# Adafruit_TFP401_to_40pin_TFT.net
KiCad netlist of a schematic drawn in EAGLE
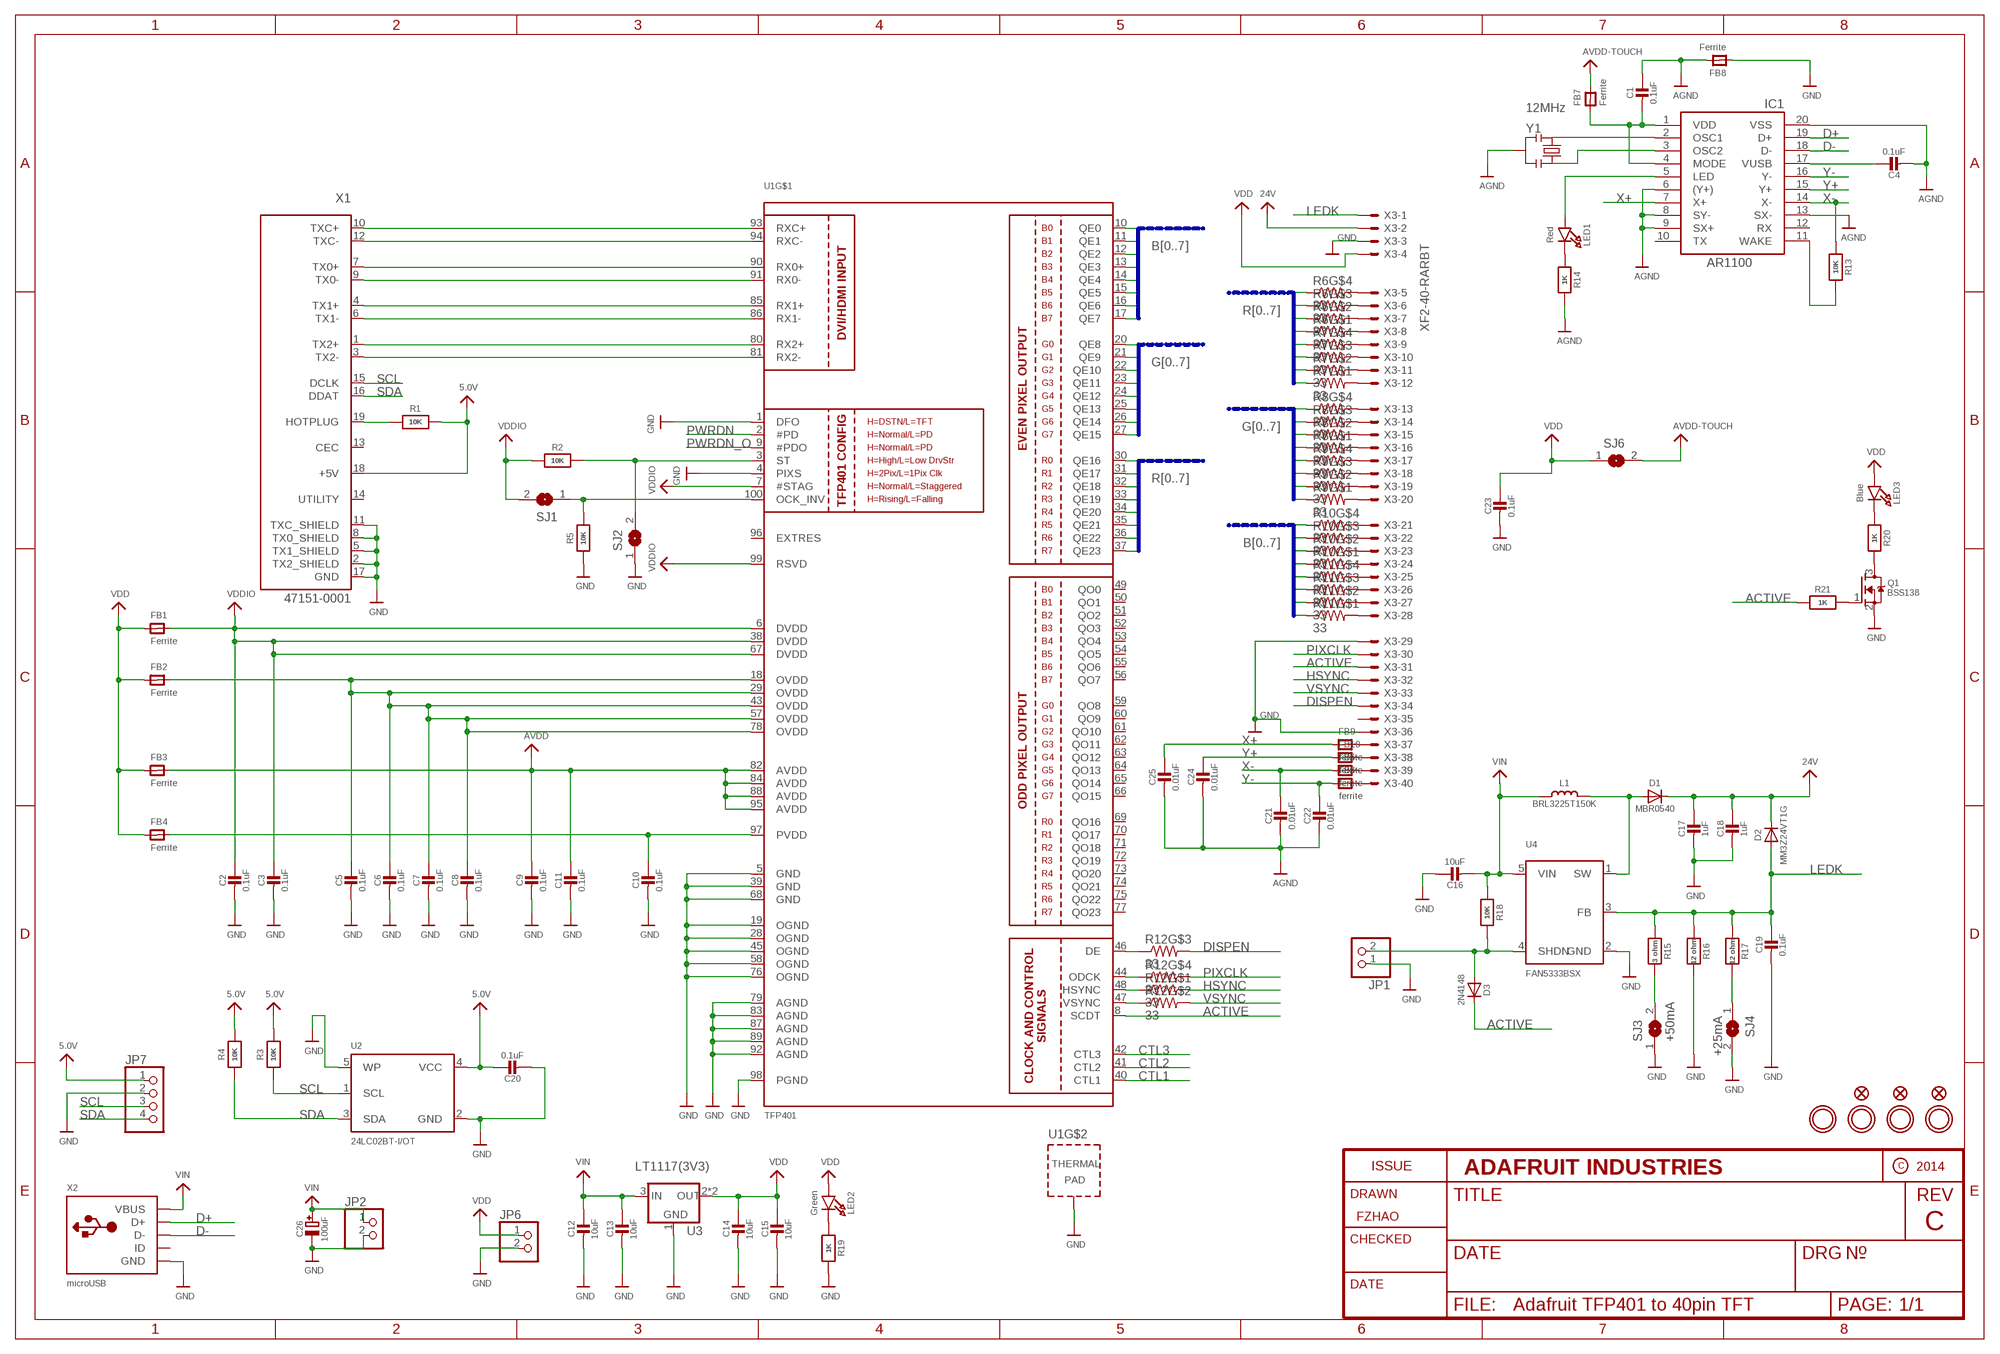
[diagram p0: schematic, sheet 1]

(export (version "E")
  (design (tool "Eeschema 10.0.6"))
  (components
    (comp (ref "C1")
      (value "0.1uF")
      (footprint "eagle-import:0805-NO")
      (libsource (lib "eagle-import") (part "CAP_CERAMIC0805-NOOUTLINE"))
    )
    (comp (ref "C2")
      (value "0.1uF")
      (footprint "eagle-import:0805-NO")
      (libsource (lib "eagle-import") (part "CAP_CERAMIC0805-NOOUTLINE"))
    )
    (comp (ref "C3")
      (value "0.1uF")
      (footprint "eagle-import:0805-NO")
      (libsource (lib "eagle-import") (part "CAP_CERAMIC0805-NOOUTLINE"))
    )
    (comp (ref "C4")
      (value "0.1uF")
      (footprint "eagle-import:0805-NO")
      (libsource (lib "eagle-import") (part "CAP_CERAMIC0805-NOOUTLINE"))
    )
    (comp (ref "C5")
      (value "0.1uF")
      (footprint "eagle-import:0805-NO")
      (libsource (lib "eagle-import") (part "CAP_CERAMIC0805-NOOUTLINE"))
    )
    (comp (ref "C6")
      (value "0.1uF")
      (footprint "eagle-import:_0805MP")
      (libsource (lib "eagle-import") (part "CAP_CERAMIC_0805MP"))
    )
    (comp (ref "C7")
      (value "0.1uF")
      (footprint "eagle-import:0805-NO")
      (libsource (lib "eagle-import") (part "CAP_CERAMIC0805-NOOUTLINE"))
    )
    (comp (ref "C8")
      (value "0.1uF")
      (footprint "eagle-import:0805-NO")
      (libsource (lib "eagle-import") (part "CAP_CERAMIC0805-NOOUTLINE"))
    )
    (comp (ref "C9")
      (value "0.1uF")
      (footprint "eagle-import:0805-NO")
      (libsource (lib "eagle-import") (part "CAP_CERAMIC0805-NOOUTLINE"))
    )
    (comp (ref "C10")
      (value "0.1uF")
      (footprint "eagle-import:0805-NO")
      (libsource (lib "eagle-import") (part "CAP_CERAMIC0805-NOOUTLINE"))
    )
    (comp (ref "C11")
      (value "0.1uF")
      (footprint "eagle-import:0805-NO")
      (libsource (lib "eagle-import") (part "CAP_CERAMIC0805-NOOUTLINE"))
    )
    (comp (ref "C12")
      (value "10uF")
      (footprint "eagle-import:0805-NO")
      (libsource (lib "eagle-import") (part "CAP_CERAMIC0805-NOOUTLINE"))
    )
    (comp (ref "C13")
      (value "10uF")
      (footprint "eagle-import:0805-NO")
      (libsource (lib "eagle-import") (part "CAP_CERAMIC0805-NOOUTLINE"))
    )
    (comp (ref "C14")
      (value "10uF")
      (footprint "eagle-import:0805-NO")
      (libsource (lib "eagle-import") (part "CAP_CERAMIC0805-NOOUTLINE"))
    )
    (comp (ref "C15")
      (value "10uF")
      (footprint "eagle-import:0805-NO")
      (libsource (lib "eagle-import") (part "CAP_CERAMIC0805-NOOUTLINE"))
    )
    (comp (ref "C16")
      (value "10uF")
      (footprint "eagle-import:0805-NO")
      (libsource (lib "eagle-import") (part "CAP_CERAMIC0805-NOOUTLINE"))
    )
    (comp (ref "C17")
      (value "1uF")
      (footprint "eagle-import:0805-NO")
      (libsource (lib "eagle-import") (part "CAP_CERAMIC0805-NOOUTLINE"))
    )
    (comp (ref "C18")
      (value "1uF")
      (footprint "eagle-import:0805-NO")
      (libsource (lib "eagle-import") (part "CAP_CERAMIC0805-NOOUTLINE"))
    )
    (comp (ref "C19")
      (value "0.1uF")
      (footprint "eagle-import:0805-NO")
      (libsource (lib "eagle-import") (part "CAP_CERAMIC0805-NOOUTLINE"))
    )
    (comp (ref "C20")
      (value "0.1uF")
      (footprint "eagle-import:0805-NO")
      (libsource (lib "eagle-import") (part "CAP_CERAMIC0805-NOOUTLINE"))
    )
    (comp (ref "C21")
      (value "0.01uF")
      (footprint "eagle-import:0805-NO")
      (libsource (lib "eagle-import") (part "CAP_CERAMIC0805-NOOUTLINE"))
    )
    (comp (ref "C22")
      (value "0.01uF")
      (footprint "eagle-import:0805-NO")
      (libsource (lib "eagle-import") (part "CAP_CERAMIC0805-NOOUTLINE"))
    )
    (comp (ref "C23")
      (value "0.1uF")
      (footprint "eagle-import:0805-NO")
      (libsource (lib "eagle-import") (part "CAP_CERAMIC0805-NOOUTLINE"))
    )
    (comp (ref "C24")
      (value "0.01uF")
      (footprint "eagle-import:0805-NO")
      (libsource (lib "eagle-import") (part "CAP_CERAMIC0805-NOOUTLINE"))
    )
    (comp (ref "C25")
      (value "0.01uF")
      (footprint "eagle-import:0805-NO")
      (libsource (lib "eagle-import") (part "CAP_CERAMIC0805-NOOUTLINE"))
    )
    (comp (ref "C26")
      (value "100uF")
      (footprint "eagle-import:PANASONIC_C")
      (libsource (lib "eagle-import") (part "CAP_ELECTROLYTICPANASONIC_C"))
    )
    (comp (ref "D1")
      (value "MBR0540")
      (footprint "eagle-import:SOD-123")
      (libsource (lib "eagle-import") (part "DIODESOD-123"))
    )
    (comp (ref "D2")
      (value "MM3Z24VT1G")
      (footprint "eagle-import:SMADIODE")
      (libsource (lib "eagle-import") (part "DIODESMA"))
    )
    (comp (ref "D3")
      (value "2N4148")
      (footprint "eagle-import:SOD-323")
      (libsource (lib "eagle-import") (part "DIODESOD-323"))
    )
    (comp (ref "FB1")
      (value "Ferrite")
      (footprint "eagle-import:_0805MP")
      (libsource (lib "eagle-import") (part "FERRITE_0805MP"))
    )
    (comp (ref "FB2")
      (value "Ferrite")
      (footprint "eagle-import:_0805MP")
      (libsource (lib "eagle-import") (part "FERRITE_0805MP"))
    )
    (comp (ref "FB3")
      (value "Ferrite")
      (footprint "eagle-import:_0805MP")
      (libsource (lib "eagle-import") (part "FERRITE_0805MP"))
    )
    (comp (ref "FB4")
      (value "Ferrite")
      (footprint "eagle-import:_0805MP")
      (libsource (lib "eagle-import") (part "FERRITE_0805MP"))
    )
    (comp (ref "FB5")
      (value "ferrite")
      (footprint "eagle-import:_0805MP")
      (libsource (lib "eagle-import") (part "FERRITE_0805MP"))
    )
    (comp (ref "FB6")
      (value "ferrite")
      (footprint "eagle-import:_0805MP")
      (libsource (lib "eagle-import") (part "FERRITE_0805MP"))
    )
    (comp (ref "FB7")
      (value "Ferrite")
      (footprint "eagle-import:_0805MP")
      (libsource (lib "eagle-import") (part "FERRITE_0805MP"))
    )
    (comp (ref "FB8")
      (value "Ferrite")
      (footprint "eagle-import:_0805MP")
      (libsource (lib "eagle-import") (part "FERRITE_0805MP"))
    )
    (comp (ref "FB9")
      (value "ferrite")
      (footprint "eagle-import:_0805MP")
      (libsource (lib "eagle-import") (part "FERRITE_0805MP"))
    )
    (comp (ref "FB10")
      (value "ferrite")
      (footprint "eagle-import:_0805MP")
      (libsource (lib "eagle-import") (part "FERRITE_0805MP"))
    )
    (comp (ref "FID1")
      (value "FIDUCIAL\"\"")
      (footprint "eagle-import:FIDUCIAL_1MM")
      (libsource (lib "eagle-import") (part "FIDUCIAL{dblquote}{dblquote}"))
    )
    (comp (ref "FID2")
      (value "FIDUCIAL\"\"")
      (footprint "eagle-import:FIDUCIAL_1MM")
      (libsource (lib "eagle-import") (part "FIDUCIAL{dblquote}{dblquote}"))
    )
    (comp (ref "FID3")
      (value "FIDUCIAL\"\"")
      (footprint "eagle-import:FIDUCIAL_1MM")
      (libsource (lib "eagle-import") (part "FIDUCIAL{dblquote}{dblquote}"))
    )
    (comp (ref "IC1")
      (value "AR1100_SSOP")
      (footprint "eagle-import:TSSOP20-5.3MMBODY")
      (libsource (lib "eagle-import") (part "AR1100_SSOP"))
    )
    (comp (ref "JP1")
      (value "HEADER-1X2ROUND")
      (footprint "eagle-import:1X02_ROUND")
      (libsource (lib "eagle-import") (part "HEADER-1X2ROUND"))
    )
    (comp (ref "JP2")
      (value "HEADER-1X2ROUND")
      (footprint "eagle-import:1X02_ROUND")
      (libsource (lib "eagle-import") (part "HEADER-1X2ROUND"))
    )
    (comp (ref "JP6")
      (value "HEADER-1X2ROUND")
      (footprint "eagle-import:1X02_ROUND")
      (libsource (lib "eagle-import") (part "HEADER-1X2ROUND"))
    )
    (comp (ref "JP7")
      (value "HEADER-1X476MIL")
      (footprint "eagle-import:1X04_ROUND_76")
      (libsource (lib "eagle-import") (part "HEADER-1X476MIL"))
    )
    (comp (ref "L1")
      (value "BRL3225T150K")
      (footprint "eagle-import:INDUCTOR_5X5MM_NR5040_NOTHERMALS")
      (libsource (lib "eagle-import") (part "INDUCTORNR5040"))
    )
    (comp (ref "LED1")
      (value "Red")
      (footprint "eagle-import:CHIPLED_0805_NOOUTLINE")
      (libsource (lib "eagle-import") (part "LED0805_NOOUTLINE"))
    )
    (comp (ref "LED2")
      (value "Green")
      (footprint "eagle-import:CHIPLED_0805_NOOUTLINE")
      (libsource (lib "eagle-import") (part "LED0805_NOOUTLINE"))
    )
    (comp (ref "LED3")
      (value "Blue")
      (footprint "eagle-import:CHIPLED_0805_NOOUTLINE")
      (libsource (lib "eagle-import") (part "LED0805_NOOUTLINE"))
    )
    (comp (ref "Q1")
      (value "BSS138")
      (footprint "eagle-import:SOT23-R")
      (libsource (lib "eagle-import") (part "MOSFET-NREFLOW"))
    )
    (comp (ref "R1")
      (value "10K")
      (footprint "eagle-import:0805-NO")
      (libsource (lib "eagle-import") (part "RESISTOR0805_NOOUTLINE"))
    )
    (comp (ref "R2")
      (value "10K")
      (footprint "eagle-import:0805-NO")
      (libsource (lib "eagle-import") (part "RESISTOR0805_NOOUTLINE"))
    )
    (comp (ref "R3")
      (value "10K")
      (footprint "eagle-import:0805-NO")
      (libsource (lib "eagle-import") (part "RESISTOR0805_NOOUTLINE"))
    )
    (comp (ref "R4")
      (value "10K")
      (footprint "eagle-import:0805-NO")
      (libsource (lib "eagle-import") (part "RESISTOR0805_NOOUTLINE"))
    )
    (comp (ref "R5")
      (value "10K")
      (footprint "eagle-import:_0805MP")
      (libsource (lib "eagle-import") (part "RESISTOR_0805MP"))
    )
    (comp (ref "R6")
      (value "33")
      (footprint "eagle-import:RESPACK_4X0603")
      (libsource (lib "eagle-import") (part "RESISTOR_4PACK_US"))
    )
    (comp (ref "R7")
      (value "33")
      (footprint "eagle-import:RESPACK_4X0603")
      (libsource (lib "eagle-import") (part "RESISTOR_4PACK_US"))
    )
    (comp (ref "R8")
      (value "33")
      (footprint "eagle-import:RESPACK_4X0603")
      (libsource (lib "eagle-import") (part "RESISTOR_4PACK_US"))
    )
    (comp (ref "R9")
      (value "33")
      (footprint "eagle-import:RESPACK_4X0603")
      (libsource (lib "eagle-import") (part "RESISTOR_4PACK_US"))
    )
    (comp (ref "R10")
      (value "33")
      (footprint "eagle-import:RESPACK_4X0603")
      (libsource (lib "eagle-import") (part "RESISTOR_4PACK_US"))
    )
    (comp (ref "R11")
      (value "33")
      (footprint "eagle-import:RESPACK_4X0603")
      (libsource (lib "eagle-import") (part "RESISTOR_4PACK_US"))
    )
    (comp (ref "R12")
      (value "33")
      (footprint "eagle-import:RESPACK_4X0603")
      (libsource (lib "eagle-import") (part "RESISTOR_4PACK_US"))
    )
    (comp (ref "R13")
      (value "10K")
      (footprint "eagle-import:_0805MP")
      (libsource (lib "eagle-import") (part "RESISTOR_0805MP"))
    )
    (comp (ref "R14")
      (value "1K")
      (footprint "eagle-import:0805-NO")
      (libsource (lib "eagle-import") (part "RESISTOR0805_NOOUTLINE"))
    )
    (comp (ref "R15")
      (value "3 ohm")
      (footprint "eagle-import:0805-NO")
      (libsource (lib "eagle-import") (part "RESISTOR0805_NOOUTLINE"))
    )
    (comp (ref "R16")
      (value "12 ohm")
      (footprint "eagle-import:0805-NO")
      (libsource (lib "eagle-import") (part "RESISTOR0805_NOOUTLINE"))
    )
    (comp (ref "R17")
      (value "12 ohm")
      (footprint "eagle-import:0805-NO")
      (libsource (lib "eagle-import") (part "RESISTOR0805_NOOUTLINE"))
    )
    (comp (ref "R18")
      (value "10K")
      (footprint "eagle-import:0805-NO")
      (libsource (lib "eagle-import") (part "RESISTOR0805_NOOUTLINE"))
    )
    (comp (ref "R19")
      (value "1K")
      (footprint "eagle-import:0805-NO")
      (libsource (lib "eagle-import") (part "RESISTOR0805_NOOUTLINE"))
    )
    (comp (ref "R20")
      (value "1K")
      (footprint "eagle-import:0805-NO")
      (libsource (lib "eagle-import") (part "RESISTOR0805_NOOUTLINE"))
    )
    (comp (ref "R21")
      (value "1K")
      (footprint "eagle-import:0805-NO")
      (libsource (lib "eagle-import") (part "RESISTOR0805_NOOUTLINE"))
    )
    (comp (ref "SJ1")
      (value "SOLDERJUMPER")
      (footprint "eagle-import:SOLDERJUMPER_ARROW_NOPASTE")
      (libsource (lib "eagle-import") (part "SOLDERJUMPER"))
    )
    (comp (ref "SJ2")
      (value "SOLDERJUMPER")
      (footprint "eagle-import:SOLDERJUMPER_ARROW_NOPASTE")
      (fields (field (name "BOM") "EXCLUDE"))
      (libsource (lib "eagle-import") (part "SOLDERJUMPER"))
    )
    (comp (ref "SJ3")
      (value "+50mA")
      (footprint "eagle-import:SOLDERJUMPER_ARROW_NOPASTE")
      (libsource (lib "eagle-import") (part "SOLDERJUMPER"))
    )
    (comp (ref "SJ4")
      (value "+25mA")
      (footprint "eagle-import:SOLDERJUMPER_ARROW_NOPASTE")
      (libsource (lib "eagle-import") (part "SOLDERJUMPER"))
    )
    (comp (ref "SJ6")
      (value "SOLDERJUMPERCLOSED")
      (footprint "eagle-import:SOLDERJUMPER_CLOSEDWIRE")
      (libsource (lib "eagle-import") (part "SOLDERJUMPERCLOSED"))
    )
    (comp (ref "U$31")
      (value "MOUNTINGHOLE3.0")
      (footprint "eagle-import:MOUNTINGHOLE_3.0_PLATED")
      (libsource (lib "eagle-import") (part "MOUNTINGHOLE3.0"))
    )
    (comp (ref "U$32")
      (value "MOUNTINGHOLE3.0")
      (footprint "eagle-import:MOUNTINGHOLE_3.0_PLATED")
      (libsource (lib "eagle-import") (part "MOUNTINGHOLE3.0"))
    )
    (comp (ref "U$33")
      (value "MOUNTINGHOLE3.0")
      (footprint "eagle-import:MOUNTINGHOLE_3.0_PLATED")
      (libsource (lib "eagle-import") (part "MOUNTINGHOLE3.0"))
    )
    (comp (ref "U$34")
      (value "MOUNTINGHOLE3.0")
      (footprint "eagle-import:MOUNTINGHOLE_3.0_PLATED")
      (libsource (lib "eagle-import") (part "MOUNTINGHOLE3.0"))
    )
    (comp (ref "U1")
      (value "TFP401")
      (footprint "eagle-import:S-PQFP-G100")
      (libsource (lib "eagle-import") (part "TFP401"))
    )
    (comp (ref "U2")
      (value "24LC02BT-I/OT")
      (footprint "eagle-import:SOT23-5")
      (libsource (lib "eagle-import") (part "EEPROM_I2C_MCP24AA32"))
    )
    (comp (ref "U3")
      (value "LT1117(3V3)")
      (footprint "eagle-import:SOT223-R")
      (libsource (lib "eagle-import") (part "VREG_SOT223"))
    )
    (comp (ref "U4")
      (value "FAN5333BSX")
      (footprint "eagle-import:SOT23-5")
      (libsource (lib "eagle-import") (part "VREG_FAN5331"))
    )
    (comp (ref "X1")
      (value "47151-0001")
      (footprint "eagle-import:HDMI_MOLEX_47151-0001_DIMLAYER")
      (libsource (lib "eagle-import") (part "HDMI_MOLEX_47151DIM"))
    )
    (comp (ref "X2")
      (value "microUSB")
      (footprint "eagle-import:4UCONN_20329")
      (libsource (lib "eagle-import") (part "USBMICRO_20329"))
    )
    (comp (ref "X3")
      (value "XF2-40-RARBT")
      (footprint "eagle-import:4-1734839-0")
      (libsource (lib "eagle-import") (part "XF2-40?-RARBT"))
    )
    (comp (ref "Y1")
      (value "12MHz")
      (footprint "eagle-import:RESONATOR-SMD")
      (libsource (lib "eagle-import") (part "RESONATORSMD"))
    )
  )
  (nets
    (net (code "1") (name "/ACTIVE") (class "Default")
      (node (ref "D3") (pin "C") (pinfunction "C_C") (pintype "passive"))
      (node (ref "R21") (pin "1") (pinfunction "1_1") (pintype "passive"))
      (node (ref "U1") (pin "8") (pinfunction "SCDT_8") (pintype "output"))
      (node (ref "X3") (pin "31") (pinfunction "MS_31") (pintype "passive"))
    )
    (net (code "2") (name "/B0") (class "Default")
      (node (ref "R10") (pin "4") (pinfunction "1_4") (pintype "passive"))
      (node (ref "U1") (pin "10") (pinfunction "QE0_10") (pintype "output"))
    )
    (net (code "3") (name "/B1") (class "Default")
      (node (ref "R10") (pin "3") (pinfunction "1_3") (pintype "passive"))
      (node (ref "U1") (pin "11") (pinfunction "QE1_11") (pintype "output"))
    )
    (net (code "4") (name "/B2") (class "Default")
      (node (ref "R10") (pin "2") (pinfunction "1_2") (pintype "passive"))
      (node (ref "U1") (pin "12") (pinfunction "QE2_12") (pintype "output"))
    )
    (net (code "5") (name "/B3") (class "Default")
      (node (ref "R10") (pin "1") (pinfunction "1_1") (pintype "passive"))
      (node (ref "U1") (pin "13") (pinfunction "QE3_13") (pintype "output"))
    )
    (net (code "6") (name "/B4") (class "Default")
      (node (ref "R11") (pin "4") (pinfunction "1_4") (pintype "passive"))
      (node (ref "U1") (pin "14") (pinfunction "QE4_14") (pintype "output"))
    )
    (net (code "7") (name "/B5") (class "Default")
      (node (ref "R11") (pin "3") (pinfunction "1_3") (pintype "passive"))
      (node (ref "U1") (pin "15") (pinfunction "QE5_15") (pintype "output"))
    )
    (net (code "8") (name "/B6") (class "Default")
      (node (ref "R11") (pin "2") (pinfunction "1_2") (pintype "passive"))
      (node (ref "U1") (pin "16") (pinfunction "QE6_16") (pintype "output"))
    )
    (net (code "9") (name "/B7") (class "Default")
      (node (ref "R11") (pin "1") (pinfunction "1_1") (pintype "passive"))
      (node (ref "U1") (pin "17") (pinfunction "QE7_17") (pintype "output"))
    )
    (net (code "11") (name "/CTL1") (class "Default")
      (node (ref "U1") (pin "40") (pinfunction "CTL1_40") (pintype "output"))
    )
    (net (code "12") (name "/CTL2") (class "Default")
      (node (ref "U1") (pin "41") (pinfunction "CTL2_41") (pintype "output"))
    )
    (net (code "13") (name "/CTL3") (class "Default")
      (node (ref "U1") (pin "42") (pinfunction "CTL3_42") (pintype "output"))
    )
    (net (code "14") (name "/D+") (class "Default")
      (node (ref "IC1") (pin "19") (pinfunction "D+_19") (pintype "bidirectional"))
      (node (ref "X2") (pin "D+") (pinfunction "D+_D+") (pintype "bidirectional"))
    )
    (net (code "15") (name "/D-") (class "Default")
      (node (ref "IC1") (pin "18") (pinfunction "D-_18") (pintype "bidirectional"))
      (node (ref "X2") (pin "D-") (pinfunction "D-_D-") (pintype "bidirectional"))
    )
    (net (code "16") (name "/DISPEN") (class "Default")
      (node (ref "R12") (pin "6") (pinfunction "2_6") (pintype "passive"))
      (node (ref "X3") (pin "34") (pinfunction "MS_34") (pintype "passive"))
    )
    (net (code "17") (name "/G0") (class "Default")
      (node (ref "R8") (pin "4") (pinfunction "1_4") (pintype "passive"))
      (node (ref "U1") (pin "20") (pinfunction "QE8_20") (pintype "output"))
    )
    (net (code "18") (name "/G1") (class "Default")
      (node (ref "R8") (pin "3") (pinfunction "1_3") (pintype "passive"))
      (node (ref "U1") (pin "21") (pinfunction "QE9_21") (pintype "output"))
    )
    (net (code "19") (name "/G2") (class "Default")
      (node (ref "R8") (pin "2") (pinfunction "1_2") (pintype "passive"))
      (node (ref "U1") (pin "22") (pinfunction "QE10_22") (pintype "output"))
    )
    (net (code "20") (name "/G3") (class "Default")
      (node (ref "R8") (pin "1") (pinfunction "1_1") (pintype "passive"))
      (node (ref "U1") (pin "23") (pinfunction "QE11_23") (pintype "output"))
    )
    (net (code "21") (name "/G4") (class "Default")
      (node (ref "R9") (pin "4") (pinfunction "1_4") (pintype "passive"))
      (node (ref "U1") (pin "24") (pinfunction "QE12_24") (pintype "output"))
    )
    (net (code "22") (name "/G5") (class "Default")
      (node (ref "R9") (pin "3") (pinfunction "1_3") (pintype "passive"))
      (node (ref "U1") (pin "25") (pinfunction "QE13_25") (pintype "output"))
    )
    (net (code "23") (name "/G6") (class "Default")
      (node (ref "R9") (pin "2") (pinfunction "1_2") (pintype "passive"))
      (node (ref "U1") (pin "26") (pinfunction "QE14_26") (pintype "output"))
    )
    (net (code "24") (name "/G7") (class "Default")
      (node (ref "R9") (pin "1") (pinfunction "1_1") (pintype "passive"))
      (node (ref "U1") (pin "27") (pinfunction "QE15_27") (pintype "output"))
    )
    (net (code "26") (name "/HSYNC") (class "Default")
      (node (ref "R12") (pin "8") (pinfunction "2_8") (pintype "passive"))
      (node (ref "X3") (pin "32") (pinfunction "MS_32") (pintype "passive"))
    )
    (net (code "27") (name "/LEDK") (class "Default")
      (node (ref "C19") (pin "1") (pinfunction "1_1") (pintype "passive"))
      (node (ref "D2") (pin "A") (pinfunction "A_A") (pintype "passive"))
      (node (ref "R15") (pin "1") (pinfunction "1_1") (pintype "passive"))
      (node (ref "R16") (pin "1") (pinfunction "1_1") (pintype "passive"))
      (node (ref "R17") (pin "1") (pinfunction "1_1") (pintype "passive"))
      (node (ref "U4") (pin "3") (pinfunction "FB_3") (pintype "bidirectional"))
      (node (ref "X3") (pin "1") (pinfunction "MSV_1") (pintype "passive"))
    )
    (net (code "28") (name "/PIXCLK") (class "Default")
      (node (ref "R12") (pin "5") (pinfunction "2_5") (pintype "passive"))
      (node (ref "X3") (pin "30") (pinfunction "MS_30") (pintype "passive"))
    )
    (net (code "29") (name "/PWRDN") (class "Default")
      (node (ref "U1") (pin "2") (pinfunction "#PD_2") (pintype "input"))
    )
    (net (code "30") (name "/PWRDN_O") (class "Default")
      (node (ref "U1") (pin "9") (pinfunction "#PDO_9") (pintype "input"))
    )
    (net (code "31") (name "/R0") (class "Default")
      (node (ref "R6") (pin "4") (pinfunction "1_4") (pintype "passive"))
      (node (ref "U1") (pin "30") (pinfunction "QE16_30") (pintype "output"))
    )
    (net (code "32") (name "/R1") (class "Default")
      (node (ref "R6") (pin "3") (pinfunction "1_3") (pintype "passive"))
      (node (ref "U1") (pin "31") (pinfunction "QE17_31") (pintype "output"))
    )
    (net (code "33") (name "/R2") (class "Default")
      (node (ref "R6") (pin "2") (pinfunction "1_2") (pintype "passive"))
      (node (ref "U1") (pin "32") (pinfunction "QE18_32") (pintype "output"))
    )
    (net (code "34") (name "/R3") (class "Default")
      (node (ref "R6") (pin "1") (pinfunction "1_1") (pintype "passive"))
      (node (ref "U1") (pin "33") (pinfunction "QE19_33") (pintype "output"))
    )
    (net (code "35") (name "/R4") (class "Default")
      (node (ref "R7") (pin "4") (pinfunction "1_4") (pintype "passive"))
      (node (ref "U1") (pin "34") (pinfunction "QE20_34") (pintype "output"))
    )
    (net (code "36") (name "/R5") (class "Default")
      (node (ref "R7") (pin "3") (pinfunction "1_3") (pintype "passive"))
      (node (ref "U1") (pin "35") (pinfunction "QE21_35") (pintype "output"))
    )
    (net (code "37") (name "/R6") (class "Default")
      (node (ref "R7") (pin "2") (pinfunction "1_2") (pintype "passive"))
      (node (ref "U1") (pin "36") (pinfunction "QE22_36") (pintype "output"))
    )
    (net (code "38") (name "/R7") (class "Default")
      (node (ref "R7") (pin "1") (pinfunction "1_1") (pintype "passive"))
      (node (ref "U1") (pin "37") (pinfunction "QE23_37") (pintype "output"))
    )
    (net (code "40") (name "/SCL") (class "Default")
      (node (ref "JP7") (pin "3") (pinfunction "3_3") (pintype "passive"))
      (node (ref "R3") (pin "1") (pinfunction "1_1") (pintype "passive"))
      (node (ref "U2") (pin "1") (pinfunction "SCL_1") (pintype "bidirectional"))
      (node (ref "X1") (pin "15") (pinfunction "DCLK_15") (pintype "bidirectional"))
    )
    (net (code "41") (name "/SDA") (class "Default")
      (node (ref "JP7") (pin "4") (pinfunction "4_4") (pintype "passive"))
      (node (ref "R4") (pin "1") (pinfunction "1_1") (pintype "passive"))
      (node (ref "U2") (pin "3") (pinfunction "SDA_3") (pintype "bidirectional"))
      (node (ref "X1") (pin "16") (pinfunction "DDAT_16") (pintype "bidirectional"))
    )
    (net (code "42") (name "/VSYNC") (class "Default")
      (node (ref "R12") (pin "7") (pinfunction "2_7") (pintype "passive"))
      (node (ref "X3") (pin "33") (pinfunction "MS_33") (pintype "passive"))
    )
    (net (code "43") (name "/X+") (class "Default")
      (node (ref "C25") (pin "1") (pinfunction "1_1") (pintype "passive"))
      (node (ref "FB9") (pin "1") (pinfunction "P$1_1") (pintype "passive"))
      (node (ref "IC1") (pin "7") (pinfunction "X+_7") (pintype "bidirectional"))
    )
    (net (code "44") (name "/X-") (class "Default")
      (node (ref "C21") (pin "1") (pinfunction "1_1") (pintype "passive"))
      (node (ref "FB5") (pin "1") (pinfunction "P$1_1") (pintype "passive"))
      (node (ref "IC1") (pin "14") (pinfunction "X-_14") (pintype "bidirectional"))
      (node (ref "R13") (pin "1") (pinfunction "1_1") (pintype "passive"))
    )
    (net (code "45") (name "/Y+") (class "Default")
      (node (ref "C24") (pin "1") (pinfunction "1_1") (pintype "passive"))
      (node (ref "FB10") (pin "1") (pinfunction "P$1_1") (pintype "passive"))
      (node (ref "IC1") (pin "15") (pinfunction "Y+_15") (pintype "bidirectional"))
    )
    (net (code "46") (name "/Y-") (class "Default")
      (node (ref "C22") (pin "1") (pinfunction "1_1") (pintype "passive"))
      (node (ref "FB6") (pin "1") (pinfunction "P$1_1") (pintype "passive"))
      (node (ref "IC1") (pin "16") (pinfunction "Y-_16") (pintype "bidirectional"))
    )
    (net (code "47") (name "5.0V") (class "Default")
      (node (ref "C20") (pin "1") (pinfunction "1_1") (pintype "passive"))
      (node (ref "JP7") (pin "1") (pinfunction "1_1") (pintype "passive"))
      (node (ref "R1") (pin "2") (pinfunction "2_2") (pintype "passive"))
      (node (ref "R3") (pin "2") (pinfunction "2_2") (pintype "passive"))
      (node (ref "R4") (pin "2") (pinfunction "2_2") (pintype "passive"))
      (node (ref "U2") (pin "4") (pinfunction "VCC_4") (pintype "bidirectional"))
      (node (ref "X1") (pin "18") (pinfunction "+5V_18") (pintype "power_in"))
    )
    (net (code "48") (name "24V") (class "Default")
      (node (ref "C17") (pin "1") (pinfunction "1_1") (pintype "passive"))
      (node (ref "C18") (pin "1") (pinfunction "1_1") (pintype "passive"))
      (node (ref "D1") (pin "C") (pinfunction "C_C") (pintype "passive"))
      (node (ref "D2") (pin "C") (pinfunction "C_C") (pintype "passive"))
      (node (ref "X3") (pin "2") (pinfunction "MS_2") (pintype "passive"))
    )
    (net (code "49") (name "AGND") (class "Default")
      (node (ref "C1") (pin "1") (pinfunction "1_1") (pintype "passive"))
      (node (ref "C21") (pin "2") (pinfunction "2_2") (pintype "passive"))
      (node (ref "C22") (pin "2") (pinfunction "2_2") (pintype "passive"))
      (node (ref "C24") (pin "2") (pinfunction "2_2") (pintype "passive"))
      (node (ref "C25") (pin "2") (pinfunction "2_2") (pintype "passive"))
      (node (ref "C4") (pin "2") (pinfunction "2_2") (pintype "passive"))
      (node (ref "FB8") (pin "2") (pinfunction "P$2_2") (pintype "passive"))
      (node (ref "IC1") (pin "13") (pinfunction "SX-_13") (pintype "bidirectional"))
      (node (ref "IC1") (pin "20") (pinfunction "VSS_20") (pintype "power_in"))
      (node (ref "IC1") (pin "6") (pinfunction "(Y+)_6") (pintype "bidirectional"))
      (node (ref "IC1") (pin "8") (pinfunction "SY-_8") (pintype "bidirectional"))
      (node (ref "IC1") (pin "9") (pinfunction "SX+_9") (pintype "bidirectional"))
      (node (ref "R14") (pin "2") (pinfunction "2_2") (pintype "passive"))
      (node (ref "Y1") (pin "2") (pinfunction "2_2") (pintype "passive"))
    )
    (net (code "50") (name "AVDD") (class "Default")
      (node (ref "C11") (pin "1") (pinfunction "1_1") (pintype "passive"))
      (node (ref "C9") (pin "1") (pinfunction "1_1") (pintype "passive"))
      (node (ref "FB3") (pin "2") (pinfunction "P$2_2") (pintype "passive"))
      (node (ref "U1") (pin "82") (pinfunction "AVDD_82") (pintype "power_in"))
      (node (ref "U1") (pin "84") (pinfunction "AVDD_84") (pintype "power_in"))
      (node (ref "U1") (pin "88") (pinfunction "AVDD_88") (pintype "power_in"))
      (node (ref "U1") (pin "95") (pinfunction "AVDD_95") (pintype "power_in"))
    )
    (net (code "51") (name "AVDD-TOUCH") (class "Default")
      (node (ref "FB7") (pin "2") (pinfunction "P$2_2") (pintype "passive"))
      (node (ref "SJ6") (pin "2") (pinfunction "2_2") (pintype "passive"))
    )
    (net (code "52") (name "GND") (class "Default")
      (node (ref "C10") (pin "2") (pinfunction "2_2") (pintype "passive"))
      (node (ref "C11") (pin "2") (pinfunction "2_2") (pintype "passive"))
      (node (ref "C12") (pin "2") (pinfunction "2_2") (pintype "passive"))
      (node (ref "C13") (pin "2") (pinfunction "2_2") (pintype "passive"))
      (node (ref "C14") (pin "2") (pinfunction "2_2") (pintype "passive"))
      (node (ref "C15") (pin "2") (pinfunction "2_2") (pintype "passive"))
      (node (ref "C16") (pin "1") (pinfunction "1_1") (pintype "passive"))
      (node (ref "C17") (pin "2") (pinfunction "2_2") (pintype "passive"))
      (node (ref "C18") (pin "2") (pinfunction "2_2") (pintype "passive"))
      (node (ref "C19") (pin "2") (pinfunction "2_2") (pintype "passive"))
      (node (ref "C2") (pin "2") (pinfunction "2_2") (pintype "passive"))
      (node (ref "C20") (pin "2") (pinfunction "2_2") (pintype "passive"))
      (node (ref "C23") (pin "2") (pinfunction "2_2") (pintype "passive"))
      (node (ref "C26") (pin "-") (pinfunction "-_-") (pintype "passive"))
      (node (ref "C3") (pin "2") (pinfunction "2_2") (pintype "passive"))
      (node (ref "C5") (pin "2") (pinfunction "2_2") (pintype "passive"))
      (node (ref "C6") (pin "2") (pinfunction "2_2") (pintype "passive"))
      (node (ref "C7") (pin "2") (pinfunction "2_2") (pintype "passive"))
      (node (ref "C8") (pin "2") (pinfunction "2_2") (pintype "passive"))
      (node (ref "C9") (pin "2") (pinfunction "2_2") (pintype "passive"))
      (node (ref "FB8") (pin "1") (pinfunction "P$1_1") (pintype "passive"))
      (node (ref "JP1") (pin "1") (pinfunction "1_1") (pintype "passive"))
      (node (ref "JP2") (pin "2") (pinfunction "2_2") (pintype "passive"))
      (node (ref "JP6") (pin "2") (pinfunction "2_2") (pintype "passive"))
      (node (ref "JP7") (pin "2") (pinfunction "2_2") (pintype "passive"))
      (node (ref "Q1") (pin "2") (pinfunction "S_2") (pintype "bidirectional"))
      (node (ref "R16") (pin "2") (pinfunction "2_2") (pintype "passive"))
      (node (ref "R19") (pin "2") (pinfunction "2_2") (pintype "passive"))
      (node (ref "R5") (pin "1") (pinfunction "1_1") (pintype "passive"))
      (node (ref "SJ2") (pin "1") (pinfunction "1_1") (pintype "passive"))
      (node (ref "SJ3") (pin "1") (pinfunction "1_1") (pintype "passive"))
      (node (ref "SJ4") (pin "2") (pinfunction "2_2") (pintype "passive"))
      (node (ref "U1") (pin "1") (pinfunction "DFO_1") (pintype "input"))
      (node (ref "U1") (pin "19") (pinfunction "OGND_19") (pintype "power_in"))
      (node (ref "U1") (pin "28") (pinfunction "OGND_28") (pintype "power_in"))
      (node (ref "U1") (pin "39") (pinfunction "GND_39") (pintype "power_in"))
      (node (ref "U1") (pin "4") (pinfunction "PIXS_4") (pintype "input"))
      (node (ref "U1") (pin "45") (pinfunction "OGND_45") (pintype "power_in"))
      (node (ref "U1") (pin "5") (pinfunction "GND_5") (pintype "power_in"))
      (node (ref "U1") (pin "58") (pinfunction "OGND_58") (pintype "power_in"))
      (node (ref "U1") (pin "68") (pinfunction "GND_68") (pintype "power_in"))
      (node (ref "U1") (pin "76") (pinfunction "OGND_76") (pintype "power_in"))
      (node (ref "U1") (pin "79") (pinfunction "AGND_79") (pintype "power_in"))
      (node (ref "U1") (pin "83") (pinfunction "AGND_83") (pintype "power_in"))
      (node (ref "U1") (pin "87") (pinfunction "AGND_87") (pintype "power_in"))
      (node (ref "U1") (pin "89") (pinfunction "AGND_89") (pintype "power_in"))
      (node (ref "U1") (pin "92") (pinfunction "AGND_92") (pintype "power_in"))
      (node (ref "U1") (pin "98") (pinfunction "PGND_98") (pintype "power_in"))
      (node (ref "U1") (pin "P$1") (pinfunction "TP_P$1") (pintype "power_in"))
      (node (ref "U1") (pin "P$10") (pinfunction "TP_P$10") (pintype "power_in"))
      (node (ref "U1") (pin "P$11") (pinfunction "TP_P$11") (pintype "power_in"))
      (node (ref "U1") (pin "P$12") (pinfunction "TP_P$12") (pintype "power_in"))
      (node (ref "U1") (pin "P$13") (pinfunction "TP_P$13") (pintype "power_in"))
      (node (ref "U1") (pin "P$14") (pinfunction "TP_P$14") (pintype "power_in"))
      (node (ref "U1") (pin "P$15") (pinfunction "TP_P$15") (pintype "power_in"))
      (node (ref "U1") (pin "P$16") (pinfunction "TP_P$16") (pintype "power_in"))
      (node (ref "U1") (pin "P$2") (pinfunction "TP_P$2") (pintype "power_in"))
      (node (ref "U1") (pin "P$3") (pinfunction "TP_P$3") (pintype "power_in"))
      (node (ref "U1") (pin "P$4") (pinfunction "TP_P$4") (pintype "power_in"))
      (node (ref "U1") (pin "P$5") (pinfunction "TP_P$5") (pintype "power_in"))
      (node (ref "U1") (pin "P$6") (pinfunction "TP_P$6") (pintype "power_in"))
      (node (ref "U1") (pin "P$7") (pinfunction "TP_P$7") (pintype "power_in"))
      (node (ref "U1") (pin "P$8") (pinfunction "TP_P$8") (pintype "power_in"))
      (node (ref "U1") (pin "P$9") (pinfunction "TP_P$9") (pintype "power_in"))
      (node (ref "U1") (pin "THERMAL") (pinfunction "TP_THERMAL") (pintype "power_in"))
      (node (ref "U2") (pin "2") (pinfunction "GND_2") (pintype "bidirectional"))
      (node (ref "U2") (pin "5") (pinfunction "WP_5") (pintype "bidirectional"))
      (node (ref "U3") (pin "1") (pinfunction "GND_1") (pintype "power_in"))
      (node (ref "U4") (pin "2") (pinfunction "GND_2") (pintype "bidirectional"))
      (node (ref "X1") (pin "11") (pinfunction "TXC_SHIELD_11") (pintype "power_in"))
      (node (ref "X1") (pin "17") (pinfunction "GND_17") (pintype "power_in"))
      (node (ref "X1") (pin "2") (pinfunction "TX2_SHIELD_2") (pintype "power_in"))
      (node (ref "X1") (pin "5") (pinfunction "TX1_SHIELD_5") (pintype "power_in"))
      (node (ref "X1") (pin "8") (pinfunction "TX0_SHIELD_8") (pintype "power_in"))
      (node (ref "X2") (pin "BASE@1") (pinfunction "GND_BASE@1") (pintype "power_in"))
      (node (ref "X2") (pin "BASE@2") (pinfunction "GND_BASE@2") (pintype "power_in"))
      (node (ref "X2") (pin "GND") (pinfunction "GND_GND") (pintype "power_in"))
      (node (ref "X2") (pin "SPRT@1") (pinfunction "GND_SPRT@1") (pintype "power_in"))
      (node (ref "X2") (pin "SPRT@2") (pinfunction "GND_SPRT@2") (pintype "power_in"))
      (node (ref "X2") (pin "SPRT@3") (pinfunction "GND_SPRT@3") (pintype "power_in"))
      (node (ref "X2") (pin "SPRT@4") (pinfunction "GND_SPRT@4") (pintype "power_in"))
      (node (ref "X3") (pin "29") (pinfunction "MS_29") (pintype "passive"))
      (node (ref "X3") (pin "3") (pinfunction "MS_3") (pintype "passive"))
      (node (ref "X3") (pin "36") (pinfunction "MS_36") (pintype "passive"))
    )
    (net (code "53") (name "Net-(FB2-P$2)") (class "Default")
      (node (ref "C5") (pin "1") (pinfunction "1_1") (pintype "passive"))
      (node (ref "C6") (pin "1") (pinfunction "1_1") (pintype "passive"))
      (node (ref "C7") (pin "1") (pinfunction "1_1") (pintype "passive"))
      (node (ref "C8") (pin "1") (pinfunction "1_1") (pintype "passive"))
      (node (ref "FB2") (pin "2") (pinfunction "P$2_2") (pintype "passive"))
      (node (ref "U1") (pin "18") (pinfunction "OVDD_18") (pintype "power_in"))
      (node (ref "U1") (pin "29") (pinfunction "OVDD_29") (pintype "power_in"))
      (node (ref "U1") (pin "43") (pinfunction "OVDD_43") (pintype "power_in"))
      (node (ref "U1") (pin "57") (pinfunction "OVDD_57") (pintype "power_in"))
      (node (ref "U1") (pin "78") (pinfunction "OVDD_78") (pintype "power_in"))
    )
    (net (code "54") (name "Net-(FB4-P$2)") (class "Default")
      (node (ref "C10") (pin "1") (pinfunction "1_1") (pintype "passive"))
      (node (ref "FB4") (pin "2") (pinfunction "P$2_2") (pintype "passive"))
      (node (ref "U1") (pin "97") (pinfunction "PVDD_97") (pintype "power_in"))
    )
    (net (code "55") (name "Net-(FB5-P$2)") (class "Default")
      (node (ref "FB5") (pin "2") (pinfunction "P$2_2") (pintype "passive"))
      (node (ref "X3") (pin "39") (pinfunction "MS_39") (pintype "passive"))
    )
    (net (code "56") (name "Net-(FB6-P$2)") (class "Default")
      (node (ref "FB6") (pin "2") (pinfunction "P$2_2") (pintype "passive"))
      (node (ref "X3") (pin "40") (pinfunction "MS_40") (pintype "passive"))
    )
    (net (code "57") (name "Net-(FB7-P$1)") (class "Default")
      (node (ref "C1") (pin "2") (pinfunction "2_2") (pintype "passive"))
      (node (ref "FB7") (pin "1") (pinfunction "P$1_1") (pintype "passive"))
      (node (ref "IC1") (pin "1") (pinfunction "VDD_1") (pintype "power_in"))
      (node (ref "IC1") (pin "4") (pinfunction "MODE_4") (pintype "input"))
    )
    (net (code "58") (name "Net-(FB9-P$2)") (class "Default")
      (node (ref "FB9") (pin "2") (pinfunction "P$2_2") (pintype "passive"))
      (node (ref "X3") (pin "37") (pinfunction "MS_37") (pintype "passive"))
    )
    (net (code "59") (name "Net-(FB10-P$2)") (class "Default")
      (node (ref "FB10") (pin "2") (pinfunction "P$2_2") (pintype "passive"))
      (node (ref "X3") (pin "38") (pinfunction "MS_38") (pintype "passive"))
    )
    (net (code "60") (name "Net-(IC1-LED)") (class "Default")
      (node (ref "IC1") (pin "5") (pinfunction "LED_5") (pintype "output"))
      (node (ref "LED1") (pin "A") (pinfunction "A_A") (pintype "passive"))
    )
    (net (code "61") (name "Net-(IC1-OSC1)") (class "Default")
      (node (ref "IC1") (pin "2") (pinfunction "OSC1_2") (pintype "passive"))
      (node (ref "Y1") (pin "1") (pinfunction "1_1") (pintype "passive"))
    )
    (net (code "62") (name "Net-(IC1-OSC2)") (class "Default")
      (node (ref "IC1") (pin "3") (pinfunction "OSC2_3") (pintype "passive"))
      (node (ref "Y1") (pin "3") (pinfunction "3_3") (pintype "passive"))
    )
    (net (code "63") (name "Net-(IC1-VUSB)") (class "Default")
      (node (ref "C4") (pin "1") (pinfunction "1_1") (pintype "passive"))
      (node (ref "IC1") (pin "17") (pinfunction "VUSB_17") (pintype "power_in"))
    )
    (net (code "64") (name "Net-(IC1-WAKE)") (class "Default")
      (node (ref "IC1") (pin "11") (pinfunction "WAKE_11") (pintype "input"))
      (node (ref "R13") (pin "2") (pinfunction "2_2") (pintype "passive"))
    )
    (net (code "65") (name "Net-(L1-2)") (class "Default")
      (node (ref "D1") (pin "A") (pinfunction "A_A") (pintype "passive"))
      (node (ref "L1") (pin "P$2") (pinfunction "2_P$2") (pintype "passive"))
      (node (ref "U4") (pin "1") (pinfunction "SW_1") (pintype "bidirectional"))
    )
    (net (code "66") (name "Net-(LED1-PadC)") (class "Default")
      (node (ref "LED1") (pin "C") (pinfunction "C_C") (pintype "passive"))
      (node (ref "R14") (pin "1") (pinfunction "1_1") (pintype "passive"))
    )
    (net (code "67") (name "Net-(LED2-PadC)") (class "Default")
      (node (ref "LED2") (pin "C") (pinfunction "C_C") (pintype "passive"))
      (node (ref "R19") (pin "1") (pinfunction "1_1") (pintype "passive"))
    )
    (net (code "68") (name "Net-(LED3-PadC)") (class "Default")
      (node (ref "LED3") (pin "C") (pinfunction "C_C") (pintype "passive"))
      (node (ref "R20") (pin "1") (pinfunction "1_1") (pintype "passive"))
    )
    (net (code "69") (name "Net-(Q1-D)") (class "Default")
      (node (ref "Q1") (pin "3") (pinfunction "D_3") (pintype "bidirectional"))
      (node (ref "R20") (pin "2") (pinfunction "2_2") (pintype "passive"))
    )
    (net (code "70") (name "Net-(Q1-G)") (class "Default")
      (node (ref "Q1") (pin "1") (pinfunction "G_1") (pintype "bidirectional"))
      (node (ref "R21") (pin "2") (pinfunction "2_2") (pintype "passive"))
    )
    (net (code "71") (name "Net-(R6A-2)") (class "Default")
      (node (ref "R6") (pin "8") (pinfunction "2_8") (pintype "passive"))
      (node (ref "X3") (pin "8") (pinfunction "MS_8") (pintype "passive"))
    )
    (net (code "72") (name "Net-(R6B-2)") (class "Default")
      (node (ref "R6") (pin "7") (pinfunction "2_7") (pintype "passive"))
      (node (ref "X3") (pin "7") (pinfunction "MS_7") (pintype "passive"))
    )
    (net (code "73") (name "Net-(R6C-2)") (class "Default")
      (node (ref "R6") (pin "6") (pinfunction "2_6") (pintype "passive"))
      (node (ref "X3") (pin "6") (pinfunction "MS_6") (pintype "passive"))
    )
    (net (code "74") (name "Net-(R6D-2)") (class "Default")
      (node (ref "R6") (pin "5") (pinfunction "2_5") (pintype "passive"))
      (node (ref "X3") (pin "5") (pinfunction "MS_5") (pintype "passive"))
    )
    (net (code "75") (name "Net-(R7A-2)") (class "Default")
      (node (ref "R7") (pin "8") (pinfunction "2_8") (pintype "passive"))
      (node (ref "X3") (pin "12") (pinfunction "MS_12") (pintype "passive"))
    )
    (net (code "76") (name "Net-(R7B-2)") (class "Default")
      (node (ref "R7") (pin "7") (pinfunction "2_7") (pintype "passive"))
      (node (ref "X3") (pin "11") (pinfunction "MS_11") (pintype "passive"))
    )
    (net (code "77") (name "Net-(R7C-2)") (class "Default")
      (node (ref "R7") (pin "6") (pinfunction "2_6") (pintype "passive"))
      (node (ref "X3") (pin "10") (pinfunction "MS_10") (pintype "passive"))
    )
    (net (code "78") (name "Net-(R7D-2)") (class "Default")
      (node (ref "R7") (pin "5") (pinfunction "2_5") (pintype "passive"))
      (node (ref "X3") (pin "9") (pinfunction "MS_9") (pintype "passive"))
    )
    (net (code "79") (name "Net-(R8A-2)") (class "Default")
      (node (ref "R8") (pin "8") (pinfunction "2_8") (pintype "passive"))
      (node (ref "X3") (pin "16") (pinfunction "MS_16") (pintype "passive"))
    )
    (net (code "80") (name "Net-(R8B-2)") (class "Default")
      (node (ref "R8") (pin "7") (pinfunction "2_7") (pintype "passive"))
      (node (ref "X3") (pin "15") (pinfunction "MS_15") (pintype "passive"))
    )
    (net (code "81") (name "Net-(R8C-2)") (class "Default")
      (node (ref "R8") (pin "6") (pinfunction "2_6") (pintype "passive"))
      (node (ref "X3") (pin "14") (pinfunction "MS_14") (pintype "passive"))
    )
    (net (code "82") (name "Net-(R8D-2)") (class "Default")
      (node (ref "R8") (pin "5") (pinfunction "2_5") (pintype "passive"))
      (node (ref "X3") (pin "13") (pinfunction "MS_13") (pintype "passive"))
    )
    (net (code "83") (name "Net-(R9A-2)") (class "Default")
      (node (ref "R9") (pin "8") (pinfunction "2_8") (pintype "passive"))
      (node (ref "X3") (pin "20") (pinfunction "MS_20") (pintype "passive"))
    )
    (net (code "84") (name "Net-(R9B-2)") (class "Default")
      (node (ref "R9") (pin "7") (pinfunction "2_7") (pintype "passive"))
      (node (ref "X3") (pin "19") (pinfunction "MS_19") (pintype "passive"))
    )
    (net (code "85") (name "Net-(R9C-2)") (class "Default")
      (node (ref "R9") (pin "6") (pinfunction "2_6") (pintype "passive"))
      (node (ref "X3") (pin "18") (pinfunction "MS_18") (pintype "passive"))
    )
    (net (code "86") (name "Net-(R9D-2)") (class "Default")
      (node (ref "R9") (pin "5") (pinfunction "2_5") (pintype "passive"))
      (node (ref "X3") (pin "17") (pinfunction "MS_17") (pintype "passive"))
    )
    (net (code "87") (name "Net-(R10A-2)") (class "Default")
      (node (ref "R10") (pin "8") (pinfunction "2_8") (pintype "passive"))
      (node (ref "X3") (pin "24") (pinfunction "MS_24") (pintype "passive"))
    )
    (net (code "88") (name "Net-(R10B-2)") (class "Default")
      (node (ref "R10") (pin "7") (pinfunction "2_7") (pintype "passive"))
      (node (ref "X3") (pin "23") (pinfunction "MS_23") (pintype "passive"))
    )
    (net (code "89") (name "Net-(R10C-2)") (class "Default")
      (node (ref "R10") (pin "6") (pinfunction "2_6") (pintype "passive"))
      (node (ref "X3") (pin "22") (pinfunction "MS_22") (pintype "passive"))
    )
    (net (code "90") (name "Net-(R10D-2)") (class "Default")
      (node (ref "R10") (pin "5") (pinfunction "2_5") (pintype "passive"))
      (node (ref "X3") (pin "21") (pinfunction "MS_21") (pintype "passive"))
    )
    (net (code "91") (name "Net-(R11A-2)") (class "Default")
      (node (ref "R11") (pin "8") (pinfunction "2_8") (pintype "passive"))
      (node (ref "X3") (pin "28") (pinfunction "MS_28") (pintype "passive"))
    )
    (net (code "92") (name "Net-(R11B-2)") (class "Default")
      (node (ref "R11") (pin "7") (pinfunction "2_7") (pintype "passive"))
      (node (ref "X3") (pin "27") (pinfunction "MS_27") (pintype "passive"))
    )
    (net (code "93") (name "Net-(R11C-2)") (class "Default")
      (node (ref "R11") (pin "6") (pinfunction "2_6") (pintype "passive"))
      (node (ref "X3") (pin "26") (pinfunction "MS_26") (pintype "passive"))
    )
    (net (code "94") (name "Net-(R11D-2)") (class "Default")
      (node (ref "R11") (pin "5") (pinfunction "2_5") (pintype "passive"))
      (node (ref "X3") (pin "25") (pinfunction "MS_25") (pintype "passive"))
    )
    (net (code "95") (name "Net-(R12B-1)") (class "Default")
      (node (ref "R12") (pin "2") (pinfunction "1_2") (pintype "passive"))
      (node (ref "U1") (pin "47") (pinfunction "VSYNC_47") (pintype "output"))
    )
    (net (code "96") (name "Net-(R12C-1)") (class "Default")
      (node (ref "R12") (pin "3") (pinfunction "1_3") (pintype "passive"))
      (node (ref "U1") (pin "46") (pinfunction "DE_46") (pintype "output"))
    )
    (net (code "97") (name "Net-(R12D-1)") (class "Default")
      (node (ref "R12") (pin "4") (pinfunction "1_4") (pintype "passive"))
      (node (ref "U1") (pin "44") (pinfunction "ODCK_44") (pintype "output"))
    )
    (net (code "98") (name "Net-(R15-Pad2)") (class "Default")
      (node (ref "R15") (pin "2") (pinfunction "2_2") (pintype "passive"))
      (node (ref "SJ3") (pin "2") (pinfunction "2_2") (pintype "passive"))
    )
    (net (code "99") (name "Net-(R17-Pad2)") (class "Default")
      (node (ref "R17") (pin "2") (pinfunction "2_2") (pintype "passive"))
      (node (ref "SJ4") (pin "1") (pinfunction "1_1") (pintype "passive"))
    )
    (net (code "100") (name "Net-(U1A-HSYNC)") (class "Default")
      (node (ref "R12") (pin "1") (pinfunction "1_1") (pintype "passive"))
      (node (ref "U1") (pin "48") (pinfunction "HSYNC_48") (pintype "output"))
    )
    (net (code "101") (name "Net-(U1A-OCK_INV)") (class "Default")
      (node (ref "R5") (pin "2") (pinfunction "2_2") (pintype "passive"))
      (node (ref "SJ1") (pin "1") (pinfunction "1_1") (pintype "passive"))
      (node (ref "U1") (pin "100") (pinfunction "OCK_INV_100") (pintype "input"))
    )
    (net (code "102") (name "Net-(U1A-RX0+)") (class "Default")
      (node (ref "U1") (pin "90") (pinfunction "RX0+_90") (pintype "input"))
      (node (ref "X1") (pin "7") (pinfunction "TX0+_7") (pintype "bidirectional"))
    )
    (net (code "103") (name "Net-(U1A-RX0-)") (class "Default")
      (node (ref "U1") (pin "91") (pinfunction "RX0-_91") (pintype "input"))
      (node (ref "X1") (pin "9") (pinfunction "TX0-_9") (pintype "bidirectional"))
    )
    (net (code "104") (name "Net-(U1A-RX1+)") (class "Default")
      (node (ref "U1") (pin "85") (pinfunction "RX1+_85") (pintype "input"))
      (node (ref "X1") (pin "4") (pinfunction "TX1+_4") (pintype "bidirectional"))
    )
    (net (code "105") (name "Net-(U1A-RX1-)") (class "Default")
      (node (ref "U1") (pin "86") (pinfunction "RX1-_86") (pintype "input"))
      (node (ref "X1") (pin "6") (pinfunction "TX1-_6") (pintype "bidirectional"))
    )
    (net (code "106") (name "Net-(U1A-RX2+)") (class "Default")
      (node (ref "U1") (pin "80") (pinfunction "RX2+_80") (pintype "input"))
      (node (ref "X1") (pin "1") (pinfunction "TX2+_1") (pintype "bidirectional"))
    )
    (net (code "107") (name "Net-(U1A-RX2-)") (class "Default")
      (node (ref "U1") (pin "81") (pinfunction "RX2-_81") (pintype "input"))
      (node (ref "X1") (pin "3") (pinfunction "TX2-_3") (pintype "bidirectional"))
    )
    (net (code "108") (name "Net-(U1A-RXC+)") (class "Default")
      (node (ref "U1") (pin "93") (pinfunction "RXC+_93") (pintype "input"))
      (node (ref "X1") (pin "10") (pinfunction "TXC+_10") (pintype "bidirectional"))
    )
    (net (code "109") (name "Net-(U1A-RXC-)") (class "Default")
      (node (ref "U1") (pin "94") (pinfunction "RXC-_94") (pintype "input"))
      (node (ref "X1") (pin "12") (pinfunction "TXC-_12") (pintype "bidirectional"))
    )
    (net (code "110") (name "Net-(U1A-ST)") (class "Default")
      (node (ref "R2") (pin "2") (pinfunction "2_2") (pintype "passive"))
      (node (ref "SJ2") (pin "2") (pinfunction "2_2") (pintype "passive"))
      (node (ref "U1") (pin "3") (pinfunction "ST_3") (pintype "input"))
    )
    (net (code "111") (name "Net-(U4-SHDN)") (class "Default")
      (node (ref "D3") (pin "A") (pinfunction "A_A") (pintype "passive"))
      (node (ref "JP1") (pin "2") (pinfunction "2_2") (pintype "passive"))
      (node (ref "R18") (pin "2") (pinfunction "2_2") (pintype "passive"))
      (node (ref "U4") (pin "4") (pinfunction "SHDN_4") (pintype "bidirectional"))
    )
    (net (code "112") (name "Net-(X1A-HOTPLUG)") (class "Default")
      (node (ref "R1") (pin "1") (pinfunction "1_1") (pintype "passive"))
      (node (ref "X1") (pin "19") (pinfunction "HOTPLUG_19") (pintype "bidirectional"))
    )
    (net (code "113") (name "VDD") (class "Default")
      (node (ref "C14") (pin "1") (pinfunction "1_1") (pintype "passive"))
      (node (ref "C15") (pin "1") (pinfunction "1_1") (pintype "passive"))
      (node (ref "C23") (pin "1") (pinfunction "1_1") (pintype "passive"))
      (node (ref "FB1") (pin "1") (pinfunction "P$1_1") (pintype "passive"))
      (node (ref "FB2") (pin "1") (pinfunction "P$1_1") (pintype "passive"))
      (node (ref "FB3") (pin "1") (pinfunction "P$1_1") (pintype "passive"))
      (node (ref "FB4") (pin "1") (pinfunction "P$1_1") (pintype "passive"))
      (node (ref "JP6") (pin "1") (pinfunction "1_1") (pintype "passive"))
      (node (ref "LED2") (pin "A") (pinfunction "A_A") (pintype "passive"))
      (node (ref "LED3") (pin "A") (pinfunction "A_A") (pintype "passive"))
      (node (ref "SJ6") (pin "1") (pinfunction "1_1") (pintype "passive"))
      (node (ref "U3") (pin "2") (pinfunction "OUT_2") (pintype "power_in"))
      (node (ref "U3") (pin "4") (pinfunction "OUT_4") (pintype "power_in"))
      (node (ref "X3") (pin "4") (pinfunction "MS_4") (pintype "passive"))
    )
    (net (code "114") (name "VDDIO") (class "Default")
      (node (ref "C2") (pin "1") (pinfunction "1_1") (pintype "passive"))
      (node (ref "C3") (pin "1") (pinfunction "1_1") (pintype "passive"))
      (node (ref "FB1") (pin "2") (pinfunction "P$2_2") (pintype "passive"))
      (node (ref "R2") (pin "1") (pinfunction "1_1") (pintype "passive"))
      (node (ref "SJ1") (pin "2") (pinfunction "2_2") (pintype "passive"))
      (node (ref "U1") (pin "38") (pinfunction "DVDD_38") (pintype "power_in"))
      (node (ref "U1") (pin "6") (pinfunction "DVDD_6") (pintype "power_in"))
      (node (ref "U1") (pin "67") (pinfunction "DVDD_67") (pintype "power_in"))
      (node (ref "U1") (pin "7") (pinfunction "#STAG_7") (pintype "input"))
      (node (ref "U1") (pin "99") (pinfunction "RSVD_99") (pintype "input"))
    )
    (net (code "115") (name "VIN") (class "Default")
      (node (ref "C12") (pin "1") (pinfunction "1_1") (pintype "passive"))
      (node (ref "C13") (pin "1") (pinfunction "1_1") (pintype "passive"))
      (node (ref "C16") (pin "2") (pinfunction "2_2") (pintype "passive"))
      (node (ref "C26") (pin "+") (pinfunction "+_+") (pintype "passive"))
      (node (ref "JP2") (pin "1") (pinfunction "1_1") (pintype "passive"))
      (node (ref "L1") (pin "P$1") (pinfunction "1_P$1") (pintype "passive"))
      (node (ref "R18") (pin "1") (pinfunction "1_1") (pintype "passive"))
      (node (ref "U3") (pin "3") (pinfunction "IN_3") (pintype "power_in"))
      (node (ref "U4") (pin "5") (pinfunction "VIN_5") (pintype "bidirectional"))
      (node (ref "X2") (pin "VBUS") (pinfunction "VBUS_VBUS") (pintype "power_in"))
    )
    (net (code "116") (name "unconnected-(IC1-RX-Pad12)") (class "Default")
      (node (ref "IC1") (pin "12") (pinfunction "RX_12") (pintype "input"))
    )
    (net (code "117") (name "unconnected-(IC1-TX-Pad10)") (class "Default")
      (node (ref "IC1") (pin "10") (pinfunction "TX_10") (pintype "output"))
    )
    (net (code "118") (name "unconnected-(U1A-EXTRES-Pad96)") (class "Default")
      (node (ref "U1") (pin "96") (pinfunction "EXTRES_96") (pintype "input"))
    )
    (net (code "119") (name "unconnected-(U1A-QO0-Pad49)") (class "Default")
      (node (ref "U1") (pin "49") (pinfunction "QO0_49") (pintype "output"))
    )
    (net (code "120") (name "unconnected-(U1A-QO1-Pad50)") (class "Default")
      (node (ref "U1") (pin "50") (pinfunction "QO1_50") (pintype "output"))
    )
    (net (code "121") (name "unconnected-(U1A-QO2-Pad51)") (class "Default")
      (node (ref "U1") (pin "51") (pinfunction "QO2_51") (pintype "output"))
    )
    (net (code "122") (name "unconnected-(U1A-QO3-Pad52)") (class "Default")
      (node (ref "U1") (pin "52") (pinfunction "QO3_52") (pintype "output"))
    )
    (net (code "123") (name "unconnected-(U1A-QO4-Pad53)") (class "Default")
      (node (ref "U1") (pin "53") (pinfunction "QO4_53") (pintype "output"))
    )
    (net (code "124") (name "unconnected-(U1A-QO5-Pad54)") (class "Default")
      (node (ref "U1") (pin "54") (pinfunction "QO5_54") (pintype "output"))
    )
    (net (code "125") (name "unconnected-(U1A-QO6-Pad55)") (class "Default")
      (node (ref "U1") (pin "55") (pinfunction "QO6_55") (pintype "output"))
    )
    (net (code "126") (name "unconnected-(U1A-QO7-Pad56)") (class "Default")
      (node (ref "U1") (pin "56") (pinfunction "QO7_56") (pintype "output"))
    )
    (net (code "127") (name "unconnected-(U1A-QO8-Pad59)") (class "Default")
      (node (ref "U1") (pin "59") (pinfunction "QO8_59") (pintype "output"))
    )
    (net (code "128") (name "unconnected-(U1A-QO9-Pad60)") (class "Default")
      (node (ref "U1") (pin "60") (pinfunction "QO9_60") (pintype "output"))
    )
    (net (code "129") (name "unconnected-(U1A-QO10-Pad61)") (class "Default")
      (node (ref "U1") (pin "61") (pinfunction "QO10_61") (pintype "output"))
    )
    (net (code "130") (name "unconnected-(U1A-QO11-Pad62)") (class "Default")
      (node (ref "U1") (pin "62") (pinfunction "QO11_62") (pintype "output"))
    )
    (net (code "131") (name "unconnected-(U1A-QO12-Pad63)") (class "Default")
      (node (ref "U1") (pin "63") (pinfunction "QO12_63") (pintype "output"))
    )
    (net (code "132") (name "unconnected-(U1A-QO13-Pad64)") (class "Default")
      (node (ref "U1") (pin "64") (pinfunction "QO13_64") (pintype "output"))
    )
    (net (code "133") (name "unconnected-(U1A-QO14-Pad65)") (class "Default")
      (node (ref "U1") (pin "65") (pinfunction "QO14_65") (pintype "output"))
    )
    (net (code "134") (name "unconnected-(U1A-QO15-Pad66)") (class "Default")
      (node (ref "U1") (pin "66") (pinfunction "QO15_66") (pintype "output"))
    )
    (net (code "135") (name "unconnected-(U1A-QO16-Pad69)") (class "Default")
      (node (ref "U1") (pin "69") (pinfunction "QO16_69") (pintype "output"))
    )
    (net (code "136") (name "unconnected-(U1A-QO17-Pad70)") (class "Default")
      (node (ref "U1") (pin "70") (pinfunction "QO17_70") (pintype "output"))
    )
    (net (code "137") (name "unconnected-(U1A-QO18-Pad71)") (class "Default")
      (node (ref "U1") (pin "71") (pinfunction "QO18_71") (pintype "output"))
    )
    (net (code "138") (name "unconnected-(U1A-QO19-Pad72)") (class "Default")
      (node (ref "U1") (pin "72") (pinfunction "QO19_72") (pintype "output"))
    )
    (net (code "139") (name "unconnected-(U1A-QO20-Pad73)") (class "Default")
      (node (ref "U1") (pin "73") (pinfunction "QO20_73") (pintype "output"))
    )
    (net (code "140") (name "unconnected-(U1A-QO21-Pad74)") (class "Default")
      (node (ref "U1") (pin "74") (pinfunction "QO21_74") (pintype "output"))
    )
    (net (code "141") (name "unconnected-(U1A-QO22-Pad75)") (class "Default")
      (node (ref "U1") (pin "75") (pinfunction "QO22_75") (pintype "output"))
    )
    (net (code "142") (name "unconnected-(U1A-QO23-Pad77)") (class "Default")
      (node (ref "U1") (pin "77") (pinfunction "QO23_77") (pintype "output"))
    )
    (net (code "143") (name "unconnected-(X1A-CEC-Pad13)") (class "Default")
      (node (ref "X1") (pin "13") (pinfunction "CEC_13") (pintype "bidirectional"))
    )
    (net (code "144") (name "unconnected-(X1A-UTILITY-Pad14)") (class "Default")
      (node (ref "X1") (pin "14") (pinfunction "UTILITY_14") (pintype "bidirectional"))
    )
    (net (code "145") (name "unconnected-(X2-PadID)") (class "Default")
      (node (ref "X2") (pin "ID") (pinfunction "ID_ID") (pintype "bidirectional"))
    )
    (net (code "146") (name "unconnected-(X3AC-MS-Pad35)") (class "Default")
      (node (ref "X3") (pin "35") (pinfunction "MS_35") (pintype "passive"))
    )
  )
)
